# shakeflasher.net
KiCad netlist of a schematic drawn in EAGLE
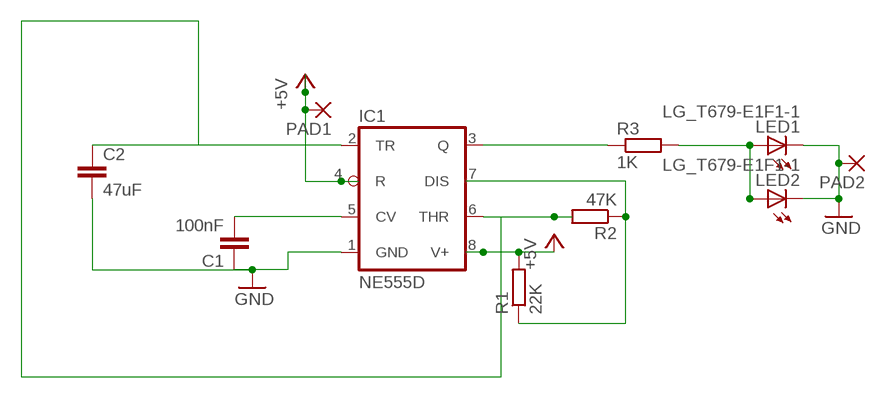
[diagram p0: schematic, sheet 1]

(export (version "E")
  (design (tool "Eeschema 10.0.6"))
  (components
    (comp (ref "C1")
      (value "100nF")
      (footprint "eagle-import:C0805")
      (libsource (lib "eagle-import") (part "C-EUC0805"))
    )
    (comp (ref "C2")
      (value "47uF")
      (footprint "eagle-import:C0805")
      (libsource (lib "eagle-import") (part "C-EUC0805"))
    )
    (comp (ref "IC1")
      (value "NE555D")
      (footprint "eagle-import:SO08")
      (libsource (lib "eagle-import") (part "555DNE"))
    )
    (comp (ref "LED1")
      (value "LG_T679-E1F1-1")
      (footprint "eagle-import:PLCC2")
      (libsource (lib "eagle-import") (part "_T679-?-1E1F1LG"))
    )
    (comp (ref "LED2")
      (value "LG_T679-E1F1-1")
      (footprint "eagle-import:PLCC2")
      (libsource (lib "eagle-import") (part "_T679-?-1E1F1LG"))
    )
    (comp (ref "PAD1")
      (value "SMD5")
      (footprint "eagle-import:SMD2,54-5,08")
      (libsource (lib "eagle-import") (part "SMD5"))
    )
    (comp (ref "PAD2")
      (value "SMD5")
      (footprint "eagle-import:SMD2,54-5,08")
      (libsource (lib "eagle-import") (part "SMD5"))
    )
    (comp (ref "R1")
      (value "22K")
      (footprint "eagle-import:R0805")
      (libsource (lib "eagle-import") (part "R-EU_R0805"))
    )
    (comp (ref "R2")
      (value "47K")
      (footprint "eagle-import:R0805")
      (libsource (lib "eagle-import") (part "R-EU_R0805"))
    )
    (comp (ref "R3")
      (value "1K")
      (footprint "eagle-import:R0805")
      (libsource (lib "eagle-import") (part "R-EU_R0805"))
    )
  )
  (nets
    (net (code "1") (name "+5V") (class "Default")
      (node (ref "IC1") (pin "4") (pinfunction "R_4") (pintype "input"))
      (node (ref "IC1") (pin "8") (pinfunction "V+_8") (pintype "power_in"))
      (node (ref "PAD1") (pin "1") (pinfunction "P_1") (pintype "passive"))
      (node (ref "R1") (pin "2") (pinfunction "2_2") (pintype "passive"))
    )
    (net (code "2") (name "GND") (class "Default")
      (node (ref "C1") (pin "1") (pinfunction "1_1") (pintype "passive"))
      (node (ref "C2") (pin "2") (pinfunction "2_2") (pintype "passive"))
      (node (ref "IC1") (pin "1") (pinfunction "GND_1") (pintype "power_in"))
      (node (ref "LED1") (pin "C") (pinfunction "C_C") (pintype "passive"))
      (node (ref "LED2") (pin "C") (pinfunction "C_C") (pintype "passive"))
      (node (ref "PAD2") (pin "1") (pinfunction "P_1") (pintype "passive"))
    )
    (net (code "3") (name "Net-(IC1-CV)") (class "Default")
      (node (ref "C1") (pin "2") (pinfunction "2_2") (pintype "passive"))
      (node (ref "IC1") (pin "5") (pinfunction "CV_5") (pintype "input"))
    )
    (net (code "4") (name "Net-(IC1-DIS)") (class "Default")
      (node (ref "IC1") (pin "7") (pinfunction "DIS_7") (pintype "input"))
      (node (ref "R1") (pin "1") (pinfunction "1_1") (pintype "passive"))
      (node (ref "R2") (pin "1") (pinfunction "1_1") (pintype "passive"))
    )
    (net (code "5") (name "Net-(IC1-Q)") (class "Default")
      (node (ref "IC1") (pin "3") (pinfunction "Q_3") (pintype "output"))
      (node (ref "R3") (pin "1") (pinfunction "1_1") (pintype "passive"))
    )
    (net (code "6") (name "Net-(IC1-THR)") (class "Default")
      (node (ref "C2") (pin "1") (pinfunction "1_1") (pintype "passive"))
      (node (ref "IC1") (pin "2") (pinfunction "TR_2") (pintype "input"))
      (node (ref "IC1") (pin "6") (pinfunction "THR_6") (pintype "input"))
      (node (ref "R2") (pin "2") (pinfunction "2_2") (pintype "passive"))
    )
    (net (code "7") (name "Net-(LED1-PadA)") (class "Default")
      (node (ref "LED1") (pin "A") (pinfunction "A_A") (pintype "passive"))
      (node (ref "LED2") (pin "A") (pinfunction "A_A") (pintype "passive"))
      (node (ref "R3") (pin "2") (pinfunction "2_2") (pintype "passive"))
    )
  )
)
